# SH24_-_ENET_PHY.net
KiCad netlist of a schematic drawn in Altium Designer
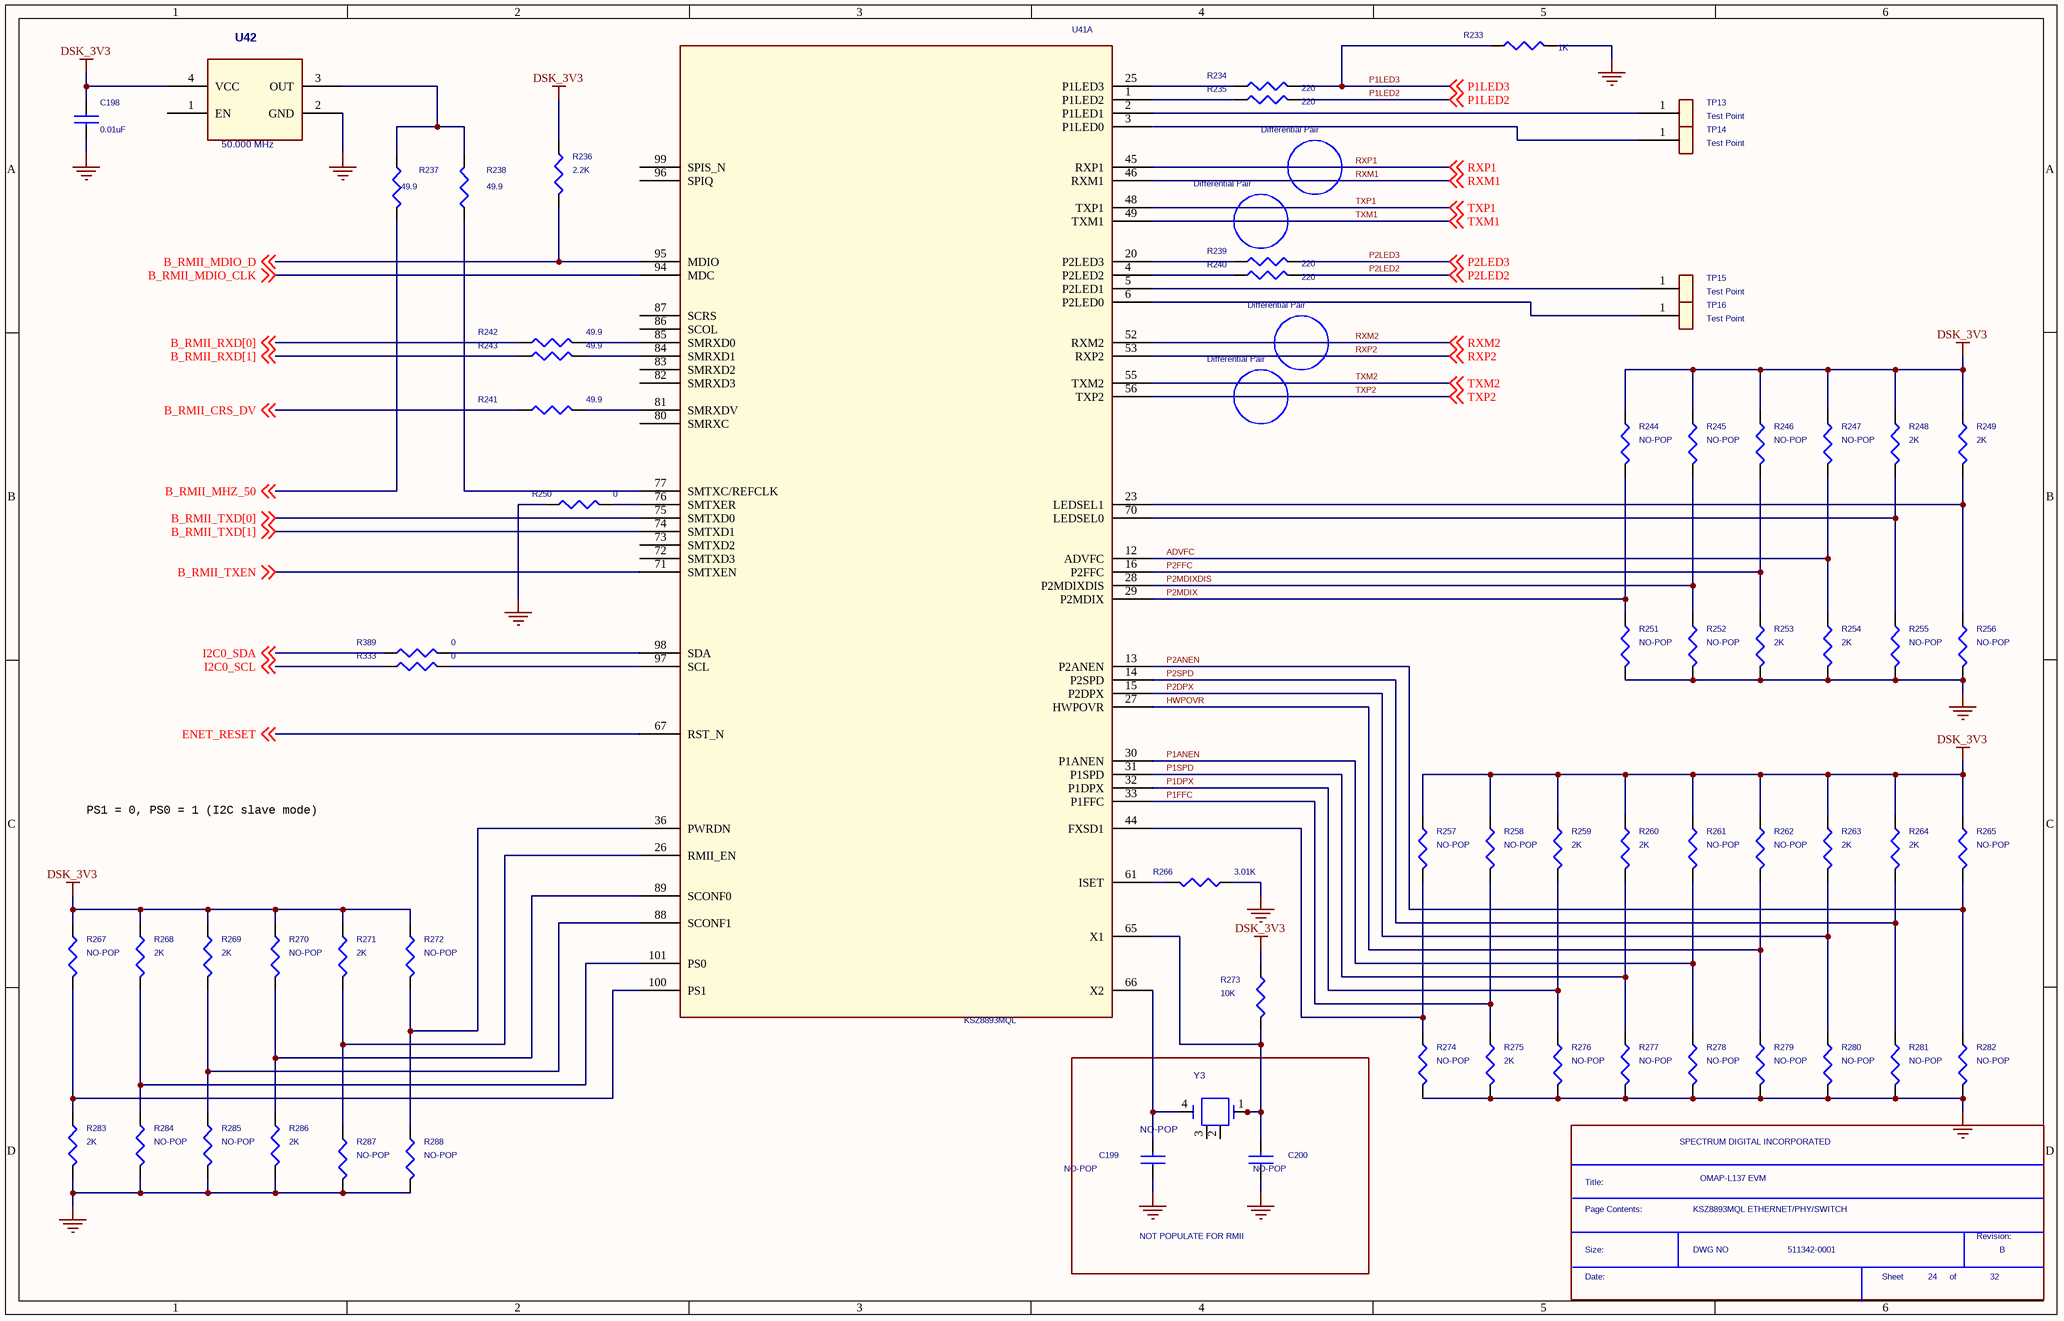
[diagram p0: SH24 - ENET PHY.SchDoc]

(export (version "E")
  (design (tool "Eeschema 10.0.6"))
  (components
    (comp (ref "C198")
      (value "0.01uF")
      (footprint "c402-25")
      (fields (field (name "PART #") "101587-1101R"))
      (libsource (lib "*") (part "CAP NP"))
    )
    (comp (ref "C199")
      (value "NO-POP")
      (footprint "c603-35x45")
      (fields (field (name "PART #") "C0603-NOPOP"))
      (libsource (lib "*") (part "CAP NP"))
    )
    (comp (ref "C200")
      (value "NO-POP")
      (footprint "c603-35x45")
      (fields (field (name "PART #") "C0603-NOPOP"))
      (libsource (lib "*") (part "CAP NP"))
    )
    (comp (ref "R233")
      (value "1K")
      (footprint "r402-25")
      (fields (field (name "PART #") "101370-1002R"))
      (libsource (lib "*") (part "RESISTOR_0"))
    )
    (comp (ref "R234")
      (value "220")
      (footprint "r402-25")
      (fields (field (name "PART #") "101370-2201R"))
      (libsource (lib "*") (part "RESISTOR_0"))
    )
    (comp (ref "R235")
      (value "220")
      (footprint "r402-25")
      (fields (field (name "PART #") "101370-2201R"))
      (libsource (lib "*") (part "RESISTOR_0"))
    )
    (comp (ref "R236")
      (value "2.2K")
      (footprint "r402-25")
      (fields (field (name "PART #") "101370-2202R"))
      (libsource (lib "*") (part "RESISTOR_0"))
    )
    (comp (ref "R237")
      (value "49.9")
      (footprint "r603-35x45")
      (fields (field (name "PART #") "100642-4990R"))
      (libsource (lib "*") (part "RESISTOR_0"))
    )
    (comp (ref "R238")
      (value "49.9")
      (footprint "r603-35x45")
      (fields (field (name "PART #") "100642-4990R"))
      (libsource (lib "*") (part "RESISTOR_0"))
    )
    (comp (ref "R239")
      (value "220")
      (footprint "r402-25")
      (fields (field (name "PART #") "101370-2201R"))
      (libsource (lib "*") (part "RESISTOR_0"))
    )
    (comp (ref "R240")
      (value "220")
      (footprint "r402-25")
      (fields (field (name "PART #") "101370-2201R"))
      (libsource (lib "*") (part "RESISTOR_0"))
    )
    (comp (ref "R241")
      (value "49.9")
      (footprint "r603-35x45")
      (fields (field (name "PART #") "100642-4990R"))
      (libsource (lib "*") (part "R"))
    )
    (comp (ref "R242")
      (value "49.9")
      (footprint "r603-35x45")
      (fields (field (name "PART #") "100642-4990R"))
      (libsource (lib "*") (part "R"))
    )
    (comp (ref "R243")
      (value "49.9")
      (footprint "r603-35x45")
      (fields (field (name "PART #") "100642-4990R"))
      (libsource (lib "*") (part "R"))
    )
    (comp (ref "R244")
      (value "NO-POP")
      (footprint "r402-25")
      (fields (field (name "PART #") "R0402-NOPOP"))
      (libsource (lib "*") (part "RESISTOR_0"))
    )
    (comp (ref "R245")
      (value "NO-POP")
      (footprint "r402-25")
      (fields (field (name "PART #") "R0402-NOPOP"))
      (libsource (lib "*") (part "RESISTOR_0"))
    )
    (comp (ref "R246")
      (value "NO-POP")
      (footprint "r402-25")
      (fields (field (name "PART #") "R0402-NOPOP"))
      (libsource (lib "*") (part "RESISTOR_0"))
    )
    (comp (ref "R247")
      (value "NO-POP")
      (footprint "r402-25")
      (fields (field (name "PART #") "R0402-NOPOP"))
      (libsource (lib "*") (part "RESISTOR_0"))
    )
    (comp (ref "R248")
      (value "2K")
      (footprint "r402-25")
      (fields (field (name "PART #") "101370-2002R"))
      (libsource (lib "*") (part "RESISTOR_0"))
    )
    (comp (ref "R249")
      (value "2K")
      (footprint "r402-25")
      (fields (field (name "PART #") "101370-2002R"))
      (libsource (lib "*") (part "RESISTOR_0"))
    )
    (comp (ref "R250")
      (value "0")
      (footprint "r402-25")
      (fields (field (name "PART #") "101370-0001R"))
      (libsource (lib "*") (part "RESISTOR_0"))
    )
    (comp (ref "R251")
      (value "NO-POP")
      (footprint "r402-25")
      (fields (field (name "PART #") "R0402-NOPOP"))
      (libsource (lib "*") (part "RESISTOR_0"))
    )
    (comp (ref "R252")
      (value "NO-POP")
      (footprint "r402-25")
      (fields (field (name "PART #") "R0402-NOPOP"))
      (libsource (lib "*") (part "RESISTOR_0"))
    )
    (comp (ref "R253")
      (value "2K")
      (footprint "r402-25")
      (fields (field (name "PART #") "101370-2002R"))
      (libsource (lib "*") (part "RESISTOR_0"))
    )
    (comp (ref "R254")
      (value "2K")
      (footprint "r402-25")
      (fields (field (name "PART #") "101370-2002R"))
      (libsource (lib "*") (part "RESISTOR_0"))
    )
    (comp (ref "R255")
      (value "NO-POP")
      (footprint "r402-25")
      (fields (field (name "PART #") "R0402-NOPOP"))
      (libsource (lib "*") (part "RESISTOR_0"))
    )
    (comp (ref "R256")
      (value "NO-POP")
      (footprint "r402-25")
      (fields (field (name "PART #") "R0402-NOPOP"))
      (libsource (lib "*") (part "RESISTOR_0"))
    )
    (comp (ref "R257")
      (value "NO-POP")
      (footprint "r402-25")
      (fields (field (name "PART #") "R0402-NOPOP"))
      (libsource (lib "*") (part "RESISTOR_0"))
    )
    (comp (ref "R258")
      (value "NO-POP")
      (footprint "r402-25")
      (fields (field (name "PART #") "R0402-NOPOP"))
      (libsource (lib "*") (part "RESISTOR_0"))
    )
    (comp (ref "R259")
      (value "2K")
      (footprint "r402-25")
      (fields (field (name "PART #") "101370-2002R"))
      (libsource (lib "*") (part "RESISTOR_0"))
    )
    (comp (ref "R260")
      (value "2K")
      (footprint "r402-25")
      (fields (field (name "PART #") "101370-2002R"))
      (libsource (lib "*") (part "RESISTOR_0"))
    )
    (comp (ref "R261")
      (value "NO-POP")
      (footprint "r402-25")
      (fields (field (name "PART #") "R0402-NOPOP"))
      (libsource (lib "*") (part "RESISTOR_0"))
    )
    (comp (ref "R262")
      (value "NO-POP")
      (footprint "r402-25")
      (fields (field (name "PART #") "R0402-NOPOP"))
      (libsource (lib "*") (part "RESISTOR_0"))
    )
    (comp (ref "R263")
      (value "2K")
      (footprint "r402-25")
      (fields (field (name "PART #") "101370-2002R"))
      (libsource (lib "*") (part "RESISTOR_0"))
    )
    (comp (ref "R264")
      (value "2K")
      (footprint "r402-25")
      (fields (field (name "PART #") "101370-2002R"))
      (libsource (lib "*") (part "RESISTOR_0"))
    )
    (comp (ref "R265")
      (value "NO-POP")
      (footprint "r402-25")
      (fields (field (name "PART #") "R0402-NOPOP"))
      (libsource (lib "*") (part "RESISTOR_0"))
    )
    (comp (ref "R266")
      (value "3.01K")
      (footprint "r603-35x45")
      (fields (field (name "PART #") "100642-3012R"))
      (libsource (lib "*") (part "RESISTOR_0"))
    )
    (comp (ref "R267")
      (value "NO-POP")
      (footprint "r402-25")
      (fields (field (name "PART #") "R0402-NOPOP"))
      (libsource (lib "*") (part "RESISTOR_0"))
    )
    (comp (ref "R268")
      (value "2K")
      (footprint "r402-25")
      (fields (field (name "PART #") "101370-2002R"))
      (libsource (lib "*") (part "RESISTOR_0"))
    )
    (comp (ref "R269")
      (value "2K")
      (footprint "r402-25")
      (fields (field (name "PART #") "101370-2002R"))
      (libsource (lib "*") (part "RESISTOR_0"))
    )
    (comp (ref "R270")
      (value "NO-POP")
      (footprint "r402-25")
      (fields (field (name "PART #") "R0402-NOPOP"))
      (libsource (lib "*") (part "RESISTOR_0"))
    )
    (comp (ref "R271")
      (value "2K")
      (footprint "r402-25")
      (fields (field (name "PART #") "101370-2002R"))
      (libsource (lib "*") (part "RESISTOR_0"))
    )
    (comp (ref "R272")
      (value "NO-POP")
      (footprint "r402-25")
      (fields (field (name "PART #") "R0402-NOPOP"))
      (libsource (lib "*") (part "RESISTOR_0"))
    )
    (comp (ref "R273")
      (value "10K")
      (footprint "r402-25")
      (fields (field (name "PART #") "101370-1003R"))
      (libsource (lib "*") (part "RESISTOR_0"))
    )
    (comp (ref "R274")
      (value "NO-POP")
      (footprint "r402-25")
      (fields (field (name "PART #") "R0402-NOPOP"))
      (libsource (lib "*") (part "RESISTOR_0"))
    )
    (comp (ref "R275")
      (value "2K")
      (footprint "r402-25")
      (fields (field (name "PART #") "101370-2002R"))
      (libsource (lib "*") (part "RESISTOR_0"))
    )
    (comp (ref "R276")
      (value "NO-POP")
      (footprint "r402-25")
      (fields (field (name "PART #") "R0402-NOPOP"))
      (libsource (lib "*") (part "RESISTOR_0"))
    )
    (comp (ref "R277")
      (value "NO-POP")
      (footprint "r402-25")
      (fields (field (name "PART #") "R0402-NOPOP"))
      (libsource (lib "*") (part "RESISTOR_0"))
    )
    (comp (ref "R278")
      (value "NO-POP")
      (footprint "r402-25")
      (fields (field (name "PART #") "R0402-NOPOP"))
      (libsource (lib "*") (part "RESISTOR_0"))
    )
    (comp (ref "R279")
      (value "NO-POP")
      (footprint "r402-25")
      (fields (field (name "PART #") "R0402-NOPOP"))
      (libsource (lib "*") (part "RESISTOR_0"))
    )
    (comp (ref "R280")
      (value "NO-POP")
      (footprint "r402-25")
      (fields (field (name "PART #") "R0402-NOPOP"))
      (libsource (lib "*") (part "RESISTOR_0"))
    )
    (comp (ref "R281")
      (value "NO-POP")
      (footprint "r402-25")
      (fields (field (name "PART #") "R0402-NOPOP"))
      (libsource (lib "*") (part "RESISTOR_0"))
    )
    (comp (ref "R282")
      (value "NO-POP")
      (footprint "r402-25")
      (fields (field (name "PART #") "R0402-NOPOP"))
      (libsource (lib "*") (part "RESISTOR_0"))
    )
    (comp (ref "R283")
      (value "2K")
      (footprint "r402-25")
      (fields (field (name "PART #") "101370-2002R"))
      (libsource (lib "*") (part "RESISTOR_0"))
    )
    (comp (ref "R284")
      (value "NO-POP")
      (footprint "r402-25")
      (fields (field (name "PART #") "R0402-NOPOP"))
      (libsource (lib "*") (part "RESISTOR_0"))
    )
    (comp (ref "R285")
      (value "NO-POP")
      (footprint "r402-25")
      (fields (field (name "PART #") "R0402-NOPOP"))
      (libsource (lib "*") (part "RESISTOR_0"))
    )
    (comp (ref "R286")
      (value "2K")
      (footprint "r402-25")
      (fields (field (name "PART #") "101370-2002R"))
      (libsource (lib "*") (part "RESISTOR_0"))
    )
    (comp (ref "R287")
      (value "NO-POP")
      (footprint "r402-25")
      (fields (field (name "PART #") "R0402-NOPOP"))
      (libsource (lib "*") (part "RESISTOR_0"))
    )
    (comp (ref "R288")
      (value "NO-POP")
      (footprint "r402-25")
      (fields (field (name "PART #") "R0402-NOPOP"))
      (libsource (lib "*") (part "RESISTOR_0"))
    )
    (comp (ref "R333")
      (value "0")
      (footprint "r402-25")
      (fields (field (name "PART #") "101370-0001R"))
      (libsource (lib "*") (part "R"))
    )
    (comp (ref "R389")
      (value "0")
      (footprint "r402-25")
      (fields (field (name "PART #") "101370-0001R"))
      (libsource (lib "*") (part "R"))
    )
    (comp (ref "TP13")
      (value "Test Point")
      (footprint "tp1-6040")
      (fields (field (name "PART #") "100115-0001R"))
      (libsource (lib "*") (part "TEST POINT"))
    )
    (comp (ref "TP14")
      (value "Test Point")
      (footprint "tp1-6040")
      (fields (field (name "PART #") "100115-0001R"))
      (libsource (lib "*") (part "TEST POINT"))
    )
    (comp (ref "TP15")
      (value "Test Point")
      (footprint "tp1-6040")
      (fields (field (name "PART #") "100115-0001R"))
      (libsource (lib "*") (part "TEST POINT"))
    )
    (comp (ref "TP16")
      (value "Test Point")
      (footprint "tp1-6040")
      (fields (field (name "PART #") "100115-0001R"))
      (libsource (lib "*") (part "TEST POINT"))
    )
    (comp (ref "U41")
      (value "KSZ8893MQL")
      (footprint "pqfp128rec-12x70")
      (fields (field (name "PART #") "102795-0001R"))
      (libsource (lib "*") (part "KS8995_multi_0"))
    )
    (comp (ref "U42")
      (value "50.000 MHz")
      (footprint "OSC4-71X79")
      (fields (field (name "PART NUMBER") "OSC-66M-01") (field (name "PART #") "100983-0050R"))
      (libsource (lib "*") (part "OSC_0"))
    )
    (comp (ref "Y3") (value "NO-POP") (footprint "xtal2-75x94") (libsource (lib "*") (part "CRYSTAL_0")))
  )
  (nets
    (net (code "1") (name "/ADVFC") (class "Default")
      (node (ref "R247") (pin "2") (pinfunction "2_2") (pintype "passive"))
      (node (ref "R254") (pin "1") (pinfunction "1_1") (pintype "passive"))
      (node (ref "U41") (pin "12") (pinfunction "ADVFC_12") (pintype "passive"))
    )
    (net (code "2") (name "/HWPOVR") (class "Default")
      (node (ref "R262") (pin "2") (pinfunction "2_2") (pintype "passive"))
      (node (ref "R279") (pin "1") (pinfunction "1_1") (pintype "passive"))
      (node (ref "U41") (pin "27") (pinfunction "HWPOVR_27") (pintype "passive"))
    )
    (net (code "3") (name "/P1ANEN") (class "Default")
      (node (ref "R261") (pin "2") (pinfunction "2_2") (pintype "passive"))
      (node (ref "R278") (pin "1") (pinfunction "1_1") (pintype "passive"))
      (node (ref "U41") (pin "30") (pinfunction "P1ANEN_30") (pintype "passive"))
    )
    (net (code "4") (name "/P1DPX") (class "Default")
      (node (ref "R259") (pin "2") (pinfunction "2_2") (pintype "passive"))
      (node (ref "R276") (pin "1") (pinfunction "1_1") (pintype "passive"))
      (node (ref "U41") (pin "32") (pinfunction "P1DPX_32") (pintype "passive"))
    )
    (net (code "5") (name "/P1FFC") (class "Default")
      (node (ref "R258") (pin "2") (pinfunction "2_2") (pintype "passive"))
      (node (ref "R275") (pin "1") (pinfunction "1_1") (pintype "passive"))
      (node (ref "U41") (pin "33") (pinfunction "P1FFC_33") (pintype "passive"))
    )
    (net (code "6") (name "/P1SPD") (class "Default")
      (node (ref "R260") (pin "2") (pinfunction "2_2") (pintype "passive"))
      (node (ref "R277") (pin "1") (pinfunction "1_1") (pintype "passive"))
      (node (ref "U41") (pin "31") (pinfunction "P1SPD_31") (pintype "passive"))
    )
    (net (code "7") (name "/P2ANEN") (class "Default")
      (node (ref "R265") (pin "2") (pinfunction "2_2") (pintype "passive"))
      (node (ref "R282") (pin "1") (pinfunction "1_1") (pintype "passive"))
      (node (ref "U41") (pin "13") (pinfunction "P2ANEN_13") (pintype "passive"))
    )
    (net (code "8") (name "/P2DPX") (class "Default")
      (node (ref "R263") (pin "2") (pinfunction "2_2") (pintype "passive"))
      (node (ref "R280") (pin "1") (pinfunction "1_1") (pintype "passive"))
      (node (ref "U41") (pin "15") (pinfunction "P2DPX_15") (pintype "passive"))
    )
    (net (code "9") (name "/P2FFC") (class "Default")
      (node (ref "R246") (pin "2") (pinfunction "2_2") (pintype "passive"))
      (node (ref "R253") (pin "1") (pinfunction "1_1") (pintype "passive"))
      (node (ref "U41") (pin "16") (pinfunction "P2FFC_16") (pintype "passive"))
    )
    (net (code "10") (name "/P2MDIX") (class "Default")
      (node (ref "R244") (pin "2") (pinfunction "2_2") (pintype "passive"))
      (node (ref "R251") (pin "1") (pinfunction "1_1") (pintype "passive"))
      (node (ref "U41") (pin "29") (pinfunction "P2MDIX_29") (pintype "passive"))
    )
    (net (code "11") (name "/P2MDIXDIS") (class "Default")
      (node (ref "R245") (pin "2") (pinfunction "2_2") (pintype "passive"))
      (node (ref "R252") (pin "1") (pinfunction "1_1") (pintype "passive"))
      (node (ref "U41") (pin "28") (pinfunction "P2MDIXDIS_28") (pintype "passive"))
    )
    (net (code "12") (name "/P2SPD") (class "Default")
      (node (ref "R264") (pin "2") (pinfunction "2_2") (pintype "passive"))
      (node (ref "R281") (pin "1") (pinfunction "1_1") (pintype "passive"))
      (node (ref "U41") (pin "14") (pinfunction "P2SPD_14") (pintype "passive"))
    )
    (net (code "13") (name "B_RMII_CRS_DV") (class "Default")
      (node (ref "R241") (pin "1") (pinfunction "1_1") (pintype "passive"))
    )
    (net (code "14") (name "B_RMII_MDIO_CLK") (class "Default")
      (node (ref "U41") (pin "94") (pinfunction "MDC_94") (pintype "passive"))
    )
    (net (code "15") (name "B_RMII_MDIO_D") (class "Default")
      (node (ref "R236") (pin "2") (pinfunction "2_2") (pintype "passive"))
      (node (ref "U41") (pin "95") (pinfunction "MDIO_95") (pintype "passive"))
    )
    (net (code "16") (name "B_RMII_MHZ_50") (class "Default")
      (node (ref "R237") (pin "1") (pinfunction "1_1") (pintype "passive"))
    )
    (net (code "17") (name "B_RMII_RXD[0]") (class "Default")
      (node (ref "R242") (pin "1") (pinfunction "1_1") (pintype "passive"))
    )
    (net (code "18") (name "B_RMII_RXD[1]") (class "Default")
      (node (ref "R243") (pin "1") (pinfunction "1_1") (pintype "passive"))
    )
    (net (code "19") (name "B_RMII_TXD[0]") (class "Default")
      (node (ref "U41") (pin "75") (pinfunction "SMTXD0_75") (pintype "passive"))
    )
    (net (code "20") (name "B_RMII_TXD[1]") (class "Default")
      (node (ref "U41") (pin "74") (pinfunction "SMTXD1_74") (pintype "passive"))
    )
    (net (code "21") (name "B_RMII_TXEN") (class "Default")
      (node (ref "U41") (pin "71") (pinfunction "SMTXEN_71") (pintype "passive"))
    )
    (net (code "22") (name "DSK_3V3") (class "Default")
      (node (ref "C198") (pin "1") (pinfunction "1_1") (pintype "passive"))
      (node (ref "R236") (pin "1") (pinfunction "1_1") (pintype "passive"))
      (node (ref "R244") (pin "1") (pinfunction "1_1") (pintype "passive"))
      (node (ref "R245") (pin "1") (pinfunction "1_1") (pintype "passive"))
      (node (ref "R246") (pin "1") (pinfunction "1_1") (pintype "passive"))
      (node (ref "R247") (pin "1") (pinfunction "1_1") (pintype "passive"))
      (node (ref "R248") (pin "1") (pinfunction "1_1") (pintype "passive"))
      (node (ref "R249") (pin "1") (pinfunction "1_1") (pintype "passive"))
      (node (ref "R257") (pin "1") (pinfunction "1_1") (pintype "passive"))
      (node (ref "R258") (pin "1") (pinfunction "1_1") (pintype "passive"))
      (node (ref "R259") (pin "1") (pinfunction "1_1") (pintype "passive"))
      (node (ref "R260") (pin "1") (pinfunction "1_1") (pintype "passive"))
      (node (ref "R261") (pin "1") (pinfunction "1_1") (pintype "passive"))
      (node (ref "R262") (pin "1") (pinfunction "1_1") (pintype "passive"))
      (node (ref "R263") (pin "1") (pinfunction "1_1") (pintype "passive"))
      (node (ref "R264") (pin "1") (pinfunction "1_1") (pintype "passive"))
      (node (ref "R265") (pin "1") (pinfunction "1_1") (pintype "passive"))
      (node (ref "R267") (pin "1") (pinfunction "1_1") (pintype "passive"))
      (node (ref "R268") (pin "1") (pinfunction "1_1") (pintype "passive"))
      (node (ref "R269") (pin "1") (pinfunction "1_1") (pintype "passive"))
      (node (ref "R270") (pin "1") (pinfunction "1_1") (pintype "passive"))
      (node (ref "R271") (pin "1") (pinfunction "1_1") (pintype "passive"))
      (node (ref "R272") (pin "1") (pinfunction "1_1") (pintype "passive"))
      (node (ref "R273") (pin "1") (pinfunction "1_1") (pintype "passive"))
      (node (ref "U42") (pin "4") (pinfunction "VCC_4") (pintype "passive"))
    )
    (net (code "23") (name "ENET_RESET") (class "Default")
      (node (ref "U41") (pin "67") (pinfunction "RST_N_67") (pintype "passive"))
    )
    (net (code "24") (name "GND") (class "Default")
      (node (ref "C198") (pin "2") (pinfunction "2_2") (pintype "passive"))
      (node (ref "C199") (pin "1") (pinfunction "1_1") (pintype "passive"))
      (node (ref "C200") (pin "1") (pinfunction "1_1") (pintype "passive"))
      (node (ref "R233") (pin "1") (pinfunction "1_1") (pintype "passive"))
      (node (ref "R250") (pin "1") (pinfunction "1_1") (pintype "passive"))
      (node (ref "R251") (pin "2") (pinfunction "2_2") (pintype "passive"))
      (node (ref "R252") (pin "2") (pinfunction "2_2") (pintype "passive"))
      (node (ref "R253") (pin "2") (pinfunction "2_2") (pintype "passive"))
      (node (ref "R254") (pin "2") (pinfunction "2_2") (pintype "passive"))
      (node (ref "R255") (pin "2") (pinfunction "2_2") (pintype "passive"))
      (node (ref "R256") (pin "2") (pinfunction "2_2") (pintype "passive"))
      (node (ref "R266") (pin "1") (pinfunction "1_1") (pintype "passive"))
      (node (ref "R274") (pin "2") (pinfunction "2_2") (pintype "passive"))
      (node (ref "R275") (pin "2") (pinfunction "2_2") (pintype "passive"))
      (node (ref "R276") (pin "2") (pinfunction "2_2") (pintype "passive"))
      (node (ref "R277") (pin "2") (pinfunction "2_2") (pintype "passive"))
      (node (ref "R278") (pin "2") (pinfunction "2_2") (pintype "passive"))
      (node (ref "R279") (pin "2") (pinfunction "2_2") (pintype "passive"))
      (node (ref "R280") (pin "2") (pinfunction "2_2") (pintype "passive"))
      (node (ref "R281") (pin "2") (pinfunction "2_2") (pintype "passive"))
      (node (ref "R282") (pin "2") (pinfunction "2_2") (pintype "passive"))
      (node (ref "R283") (pin "2") (pinfunction "2_2") (pintype "passive"))
      (node (ref "R284") (pin "2") (pinfunction "2_2") (pintype "passive"))
      (node (ref "R285") (pin "2") (pinfunction "2_2") (pintype "passive"))
      (node (ref "R286") (pin "2") (pinfunction "2_2") (pintype "passive"))
      (node (ref "R287") (pin "2") (pinfunction "2_2") (pintype "passive"))
      (node (ref "R288") (pin "2") (pinfunction "2_2") (pintype "passive"))
      (node (ref "U42") (pin "2") (pinfunction "GND_2") (pintype "passive"))
    )
    (net (code "25") (name "I2C0_SCL") (class "Default")
      (node (ref "R333") (pin "1") (pinfunction "1_1") (pintype "passive"))
    )
    (net (code "26") (name "I2C0_SDA") (class "Default")
      (node (ref "R389") (pin "1") (pinfunction "1_1") (pintype "passive"))
    )
    (net (code "27") (name "Net-(U41A-FXSD1)") (class "Default")
      (node (ref "R257") (pin "2") (pinfunction "2_2") (pintype "passive"))
      (node (ref "R274") (pin "1") (pinfunction "1_1") (pintype "passive"))
      (node (ref "U41") (pin "44") (pinfunction "FXSD1_44") (pintype "passive"))
    )
    (net (code "28") (name "Net-(U41A-ISET)") (class "Default")
      (node (ref "R266") (pin "2") (pinfunction "2_2") (pintype "passive"))
      (node (ref "U41") (pin "61") (pinfunction "ISET_61") (pintype "passive"))
    )
    (net (code "29") (name "Net-(U41A-LEDSEL0)") (class "Default")
      (node (ref "R248") (pin "2") (pinfunction "2_2") (pintype "passive"))
      (node (ref "R255") (pin "1") (pinfunction "1_1") (pintype "passive"))
      (node (ref "U41") (pin "70") (pinfunction "LEDSEL0_70") (pintype "passive"))
    )
    (net (code "30") (name "Net-(U41A-LEDSEL1)") (class "Default")
      (node (ref "R249") (pin "2") (pinfunction "2_2") (pintype "passive"))
      (node (ref "R256") (pin "1") (pinfunction "1_1") (pintype "passive"))
      (node (ref "U41") (pin "23") (pinfunction "LEDSEL1_23") (pintype "passive"))
    )
    (net (code "31") (name "Net-(U41A-P1LED0)") (class "Default")
      (node (ref "TP14") (pin "1") (pinfunction "1_1") (pintype "passive"))
      (node (ref "U41") (pin "3") (pinfunction "P1LED0_3") (pintype "passive"))
    )
    (net (code "32") (name "Net-(U41A-P1LED1)") (class "Default")
      (node (ref "TP13") (pin "1") (pinfunction "1_1") (pintype "passive"))
      (node (ref "U41") (pin "2") (pinfunction "P1LED1_2") (pintype "passive"))
    )
    (net (code "33") (name "Net-(U41A-P1LED2)") (class "Default")
      (node (ref "R235") (pin "2") (pinfunction "2_2") (pintype "passive"))
      (node (ref "U41") (pin "1") (pinfunction "P1LED2_1") (pintype "passive"))
    )
    (net (code "34") (name "Net-(U41A-P1LED3)") (class "Default")
      (node (ref "R234") (pin "2") (pinfunction "2_2") (pintype "passive"))
      (node (ref "U41") (pin "25") (pinfunction "P1LED3_25") (pintype "passive"))
    )
    (net (code "35") (name "Net-(U41A-P2LED0)") (class "Default")
      (node (ref "TP16") (pin "1") (pinfunction "1_1") (pintype "passive"))
      (node (ref "U41") (pin "6") (pinfunction "P2LED0_6") (pintype "passive"))
    )
    (net (code "36") (name "Net-(U41A-P2LED1)") (class "Default")
      (node (ref "TP15") (pin "1") (pinfunction "1_1") (pintype "passive"))
      (node (ref "U41") (pin "5") (pinfunction "P2LED1_5") (pintype "passive"))
    )
    (net (code "37") (name "Net-(U41A-P2LED2)") (class "Default")
      (node (ref "R240") (pin "2") (pinfunction "2_2") (pintype "passive"))
      (node (ref "U41") (pin "4") (pinfunction "P2LED2_4") (pintype "passive"))
    )
    (net (code "38") (name "Net-(U41A-P2LED3)") (class "Default")
      (node (ref "R239") (pin "2") (pinfunction "2_2") (pintype "passive"))
      (node (ref "U41") (pin "20") (pinfunction "P2LED3_20") (pintype "passive"))
    )
    (net (code "39") (name "Net-(U41A-PS0)") (class "Default")
      (node (ref "R268") (pin "2") (pinfunction "2_2") (pintype "passive"))
      (node (ref "R284") (pin "1") (pinfunction "1_1") (pintype "passive"))
      (node (ref "U41") (pin "101") (pinfunction "PS0_101") (pintype "passive"))
    )
    (net (code "40") (name "Net-(U41A-PS1)") (class "Default")
      (node (ref "R267") (pin "2") (pinfunction "2_2") (pintype "passive"))
      (node (ref "R283") (pin "1") (pinfunction "1_1") (pintype "passive"))
      (node (ref "U41") (pin "100") (pinfunction "PS1_100") (pintype "passive"))
    )
    (net (code "41") (name "Net-(U41A-PWRDN)") (class "Default")
      (node (ref "R272") (pin "2") (pinfunction "2_2") (pintype "passive"))
      (node (ref "R288") (pin "1") (pinfunction "1_1") (pintype "passive"))
      (node (ref "U41") (pin "36") (pinfunction "PWRDN_36") (pintype "passive"))
    )
    (net (code "42") (name "Net-(U41A-RMII_EN)") (class "Default")
      (node (ref "R271") (pin "2") (pinfunction "2_2") (pintype "passive"))
      (node (ref "R287") (pin "1") (pinfunction "1_1") (pintype "passive"))
      (node (ref "U41") (pin "26") (pinfunction "RMII_EN_26") (pintype "passive"))
    )
    (net (code "43") (name "Net-(U41A-SCL)") (class "Default")
      (node (ref "R333") (pin "2") (pinfunction "2_2") (pintype "passive"))
      (node (ref "U41") (pin "97") (pinfunction "SCL_97") (pintype "passive"))
    )
    (net (code "44") (name "Net-(U41A-SCONF0)") (class "Default")
      (node (ref "R270") (pin "2") (pinfunction "2_2") (pintype "passive"))
      (node (ref "R286") (pin "1") (pinfunction "1_1") (pintype "passive"))
      (node (ref "U41") (pin "89") (pinfunction "SCONF0_89") (pintype "passive"))
    )
    (net (code "45") (name "Net-(U41A-SCONF1)") (class "Default")
      (node (ref "R269") (pin "2") (pinfunction "2_2") (pintype "passive"))
      (node (ref "R285") (pin "1") (pinfunction "1_1") (pintype "passive"))
      (node (ref "U41") (pin "88") (pinfunction "SCONF1_88") (pintype "passive"))
    )
    (net (code "46") (name "Net-(U41A-SDA)") (class "Default")
      (node (ref "R389") (pin "2") (pinfunction "2_2") (pintype "passive"))
      (node (ref "U41") (pin "98") (pinfunction "SDA_98") (pintype "passive"))
    )
    (net (code "47") (name "Net-(U41A-SMRXD0)") (class "Default")
      (node (ref "R242") (pin "2") (pinfunction "2_2") (pintype "passive"))
      (node (ref "U41") (pin "85") (pinfunction "SMRXD0_85") (pintype "passive"))
    )
    (net (code "48") (name "Net-(U41A-SMRXD1)") (class "Default")
      (node (ref "R243") (pin "2") (pinfunction "2_2") (pintype "passive"))
      (node (ref "U41") (pin "84") (pinfunction "SMRXD1_84") (pintype "passive"))
    )
    (net (code "49") (name "Net-(U41A-SMRXDV)") (class "Default")
      (node (ref "R241") (pin "2") (pinfunction "2_2") (pintype "passive"))
      (node (ref "U41") (pin "81") (pinfunction "SMRXDV_81") (pintype "passive"))
    )
    (net (code "50") (name "Net-(U41A-SMTXC{slash}REFCLK)") (class "Default")
      (node (ref "R238") (pin "1") (pinfunction "1_1") (pintype "passive"))
      (node (ref "U41") (pin "77") (pinfunction "SMTXC/REFCLK_77") (pintype "passive"))
    )
    (net (code "51") (name "Net-(U41A-SMTXER)") (class "Default")
      (node (ref "R250") (pin "2") (pinfunction "2_2") (pintype "passive"))
      (node (ref "U41") (pin "76") (pinfunction "SMTXER_76") (pintype "passive"))
    )
    (net (code "52") (name "Net-(U41A-X1)") (class "Default")
      (node (ref "C200") (pin "2") (pinfunction "2_2") (pintype "passive"))
      (node (ref "R273") (pin "2") (pinfunction "2_2") (pintype "passive"))
      (node (ref "U41") (pin "65") (pinfunction "X1_65") (pintype "passive"))
      (node (ref "Y3") (pin "1") (pinfunction "1_1") (pintype "passive"))
    )
    (net (code "53") (name "Net-(U41A-X2)") (class "Default")
      (node (ref "C199") (pin "2") (pinfunction "2_2") (pintype "passive"))
      (node (ref "U41") (pin "66") (pinfunction "X2_66") (pintype "passive"))
      (node (ref "Y3") (pin "4") (pinfunction "4_4") (pintype "passive"))
    )
    (net (code "54") (name "Net-(U42-OUT)") (class "Default")
      (node (ref "R237") (pin "2") (pinfunction "2_2") (pintype "passive"))
      (node (ref "R238") (pin "2") (pinfunction "2_2") (pintype "passive"))
      (node (ref "U42") (pin "3") (pinfunction "OUT_3") (pintype "passive"))
    )
    (net (code "55") (name "P1LED2") (class "Default")
      (node (ref "R235") (pin "1") (pinfunction "1_1") (pintype "passive"))
    )
    (net (code "56") (name "P1LED3") (class "Default")
      (node (ref "R233") (pin "2") (pinfunction "2_2") (pintype "passive"))
      (node (ref "R234") (pin "1") (pinfunction "1_1") (pintype "passive"))
    )
    (net (code "57") (name "P2LED2") (class "Default")
      (node (ref "R240") (pin "1") (pinfunction "1_1") (pintype "passive"))
    )
    (net (code "58") (name "P2LED3") (class "Default")
      (node (ref "R239") (pin "1") (pinfunction "1_1") (pintype "passive"))
    )
    (net (code "59") (name "RXM1") (class "Default")
      (node (ref "U41") (pin "46") (pinfunction "RXM1_46") (pintype "passive"))
    )
    (net (code "60") (name "RXM2") (class "Default")
      (node (ref "U41") (pin "52") (pinfunction "RXM2_52") (pintype "passive"))
    )
    (net (code "61") (name "RXP1") (class "Default")
      (node (ref "U41") (pin "45") (pinfunction "RXP1_45") (pintype "passive"))
    )
    (net (code "62") (name "RXP2") (class "Default")
      (node (ref "U41") (pin "53") (pinfunction "RXP2_53") (pintype "passive"))
    )
    (net (code "63") (name "TXM1") (class "Default")
      (node (ref "U41") (pin "49") (pinfunction "TXM1_49") (pintype "passive"))
    )
    (net (code "64") (name "TXM2") (class "Default")
      (node (ref "U41") (pin "55") (pinfunction "TXM2_55") (pintype "passive"))
    )
    (net (code "65") (name "TXP1") (class "Default")
      (node (ref "U41") (pin "48") (pinfunction "TXP1_48") (pintype "passive"))
    )
    (net (code "66") (name "TXP2") (class "Default")
      (node (ref "U41") (pin "56") (pinfunction "TXP2_56") (pintype "passive"))
    )
    (net (code "67") (name "unconnected-(U41A-SCOL-Pad86)") (class "Default")
      (node (ref "U41") (pin "86") (pinfunction "SCOL_86") (pintype "passive"))
    )
    (net (code "68") (name "unconnected-(U41A-SCRS-Pad87)") (class "Default")
      (node (ref "U41") (pin "87") (pinfunction "SCRS_87") (pintype "passive"))
    )
    (net (code "69") (name "unconnected-(U41A-SMRXC-Pad80)") (class "Default")
      (node (ref "U41") (pin "80") (pinfunction "SMRXC_80") (pintype "passive"))
    )
    (net (code "70") (name "unconnected-(U41A-SMRXD2-Pad83)") (class "Default")
      (node (ref "U41") (pin "83") (pinfunction "SMRXD2_83") (pintype "passive"))
    )
    (net (code "71") (name "unconnected-(U41A-SMRXD3-Pad82)") (class "Default")
      (node (ref "U41") (pin "82") (pinfunction "SMRXD3_82") (pintype "passive"))
    )
    (net (code "72") (name "unconnected-(U41A-SMTXD2-Pad73)") (class "Default")
      (node (ref "U41") (pin "73") (pinfunction "SMTXD2_73") (pintype "passive"))
    )
    (net (code "73") (name "unconnected-(U41A-SMTXD3-Pad72)") (class "Default")
      (node (ref "U41") (pin "72") (pinfunction "SMTXD3_72") (pintype "passive"))
    )
    (net (code "74") (name "unconnected-(U41A-SPIQ-Pad96)") (class "Default")
      (node (ref "U41") (pin "96") (pinfunction "SPIQ_96") (pintype "passive"))
    )
    (net (code "75") (name "unconnected-(U41A-SPIS_N-Pad99)") (class "Default")
      (node (ref "U41") (pin "99") (pinfunction "SPIS_N_99") (pintype "passive"))
    )
    (net (code "76") (name "unconnected-(U42-EN-Pad1)") (class "Default")
      (node (ref "U42") (pin "1") (pinfunction "EN_1") (pintype "passive"))
    )
    (net (code "77") (name "unconnected-(Y3-Pad2)") (class "Default")
      (node (ref "Y3") (pin "2") (pinfunction "2_2") (pintype "passive"))
    )
    (net (code "78") (name "unconnected-(Y3-Pad3)") (class "Default")
      (node (ref "Y3") (pin "3") (pinfunction "3_3") (pintype "passive"))
    )
  )
)
